# FMC_Clocks.net
KiCad netlist of a schematic drawn in Altium Designer
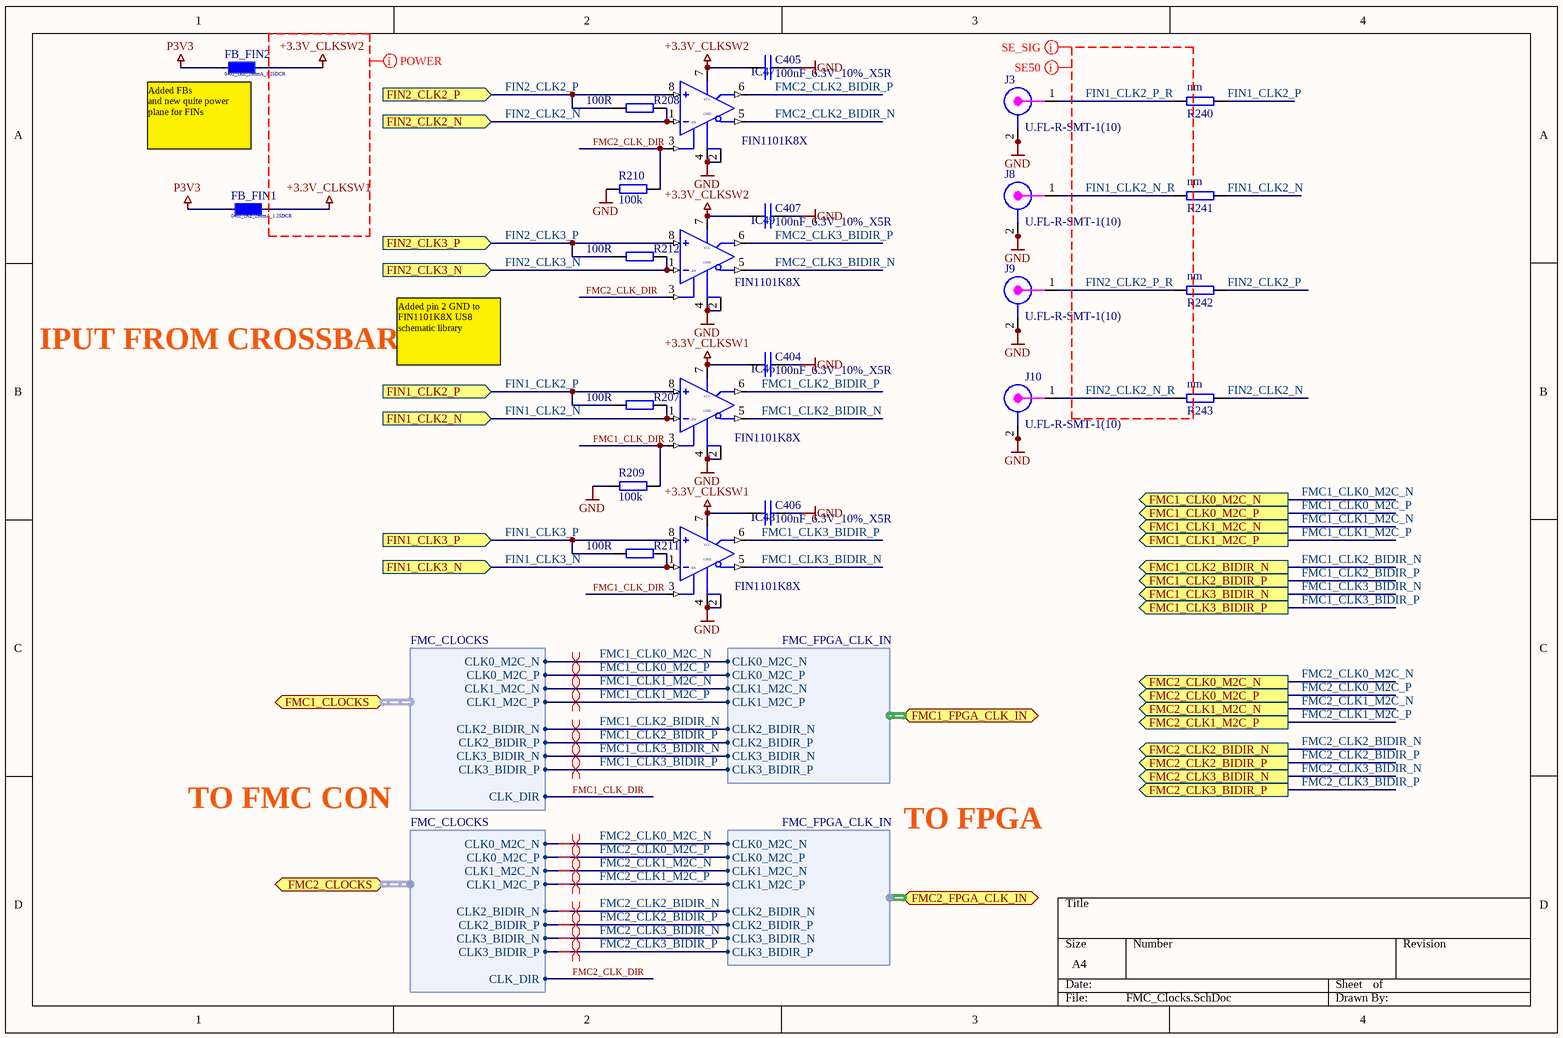
[diagram p0: FMC_Clocks.SchDoc]

(export (version "E")
  (design (tool "Eeschema 10.0.6"))
  (components
    (comp (ref "C404")
      (value "100nF_6.3V_10%_X5R")
      (footprint "0201C")
      (description "Capacitor SMD")
      (libsource (lib "LIBRARY_SCH") (part "CAP_SMD_0201"))
    )
    (comp (ref "C405")
      (value "100nF_6.3V_10%_X5R")
      (footprint "0201C")
      (description "Capacitor SMD")
      (libsource (lib "LIBRARY_SCH") (part "CAP_SMD_0201"))
    )
    (comp (ref "C406")
      (value "100nF_6.3V_10%_X5R")
      (footprint "0201C")
      (description "Capacitor SMD")
      (libsource (lib "LIBRARY_SCH") (part "CAP_SMD_0201"))
    )
    (comp (ref "C407")
      (value "100nF_6.3V_10%_X5R")
      (footprint "0201C")
      (description "Capacitor SMD")
      (libsource (lib "LIBRARY_SCH") (part "CAP_SMD_0201"))
    )
    (comp (ref "FB_FIN1")
      (value "0402_1KZ_250mA_1.25DCR")
      (footprint "INDC1005X55N")
      (description "FILTER CHIP 1000 OHM 250MA 0402")
      (fields
        (field (name "PART NUMBER") "BLM15HD102SN1D")
        (field (name "MANUFACTURER") "Murata Electronics North America")
      )
      (libsource (lib "Filters") (part "Ferrite Bead 2-pin"))
    )
    (comp (ref "FB_FIN2")
      (value "0402_1KZ_250mA_1.25DCR")
      (footprint "INDC1005X55N")
      (description "FILTER CHIP 1000 OHM 250MA 0402")
      (fields
        (field (name "PART NUMBER") "BLM15HD102SN1D")
        (field (name "MANUFACTURER") "Murata Electronics North America")
      )
      (libsource (lib "Filters") (part "Ferrite Bead 2-pin"))
    )
    (comp (ref "IC46")
      (value "FIN1101K8X")
      (footprint "US8")
      (description "LVDS TO LVDS repeater3.3V")
      (libsource (lib "AMC_FMC_Carrier") (part "IFC_FIN1101K8X"))
    )
    (comp (ref "IC47")
      (value "FIN1101K8X")
      (footprint "US8")
      (description "LVDS TO LVDS repeater3.3V")
      (libsource (lib "AMC_FMC_Carrier") (part "IFC_FIN1101K8X"))
    )
    (comp (ref "IC48")
      (value "FIN1101K8X")
      (footprint "US8")
      (description "LVDS TO LVDS repeater3.3V")
      (libsource (lib "AMC_FMC_Carrier") (part "IFC_FIN1101K8X"))
    )
    (comp (ref "IC49")
      (value "FIN1101K8X")
      (footprint "US8")
      (description "LVDS TO LVDS repeater3.3V")
      (libsource (lib "AMC_FMC_Carrier") (part "IFC_FIN1101K8X"))
    )
    (comp (ref "J3")
      (value "U.FL-R-SMT-1(10)")
      (footprint "CON_UFL_HIROSE_RECEPTACLE")
      (description "UFL")
      (libsource (lib "LIBRARY_SCH") (part "CON_UFL_SMD"))
    )
    (comp (ref "J8")
      (value "U.FL-R-SMT-1(10)")
      (footprint "CON_UFL_HIROSE_RECEPTACLE")
      (description "UFL")
      (libsource (lib "LIBRARY_SCH") (part "CON_UFL_SMD"))
    )
    (comp (ref "J9")
      (value "U.FL-R-SMT-1(10)")
      (footprint "CON_UFL_HIROSE_RECEPTACLE")
      (description "UFL")
      (libsource (lib "LIBRARY_SCH") (part "CON_UFL_SMD"))
    )
    (comp (ref "J10")
      (value "U.FL-R-SMT-1(10)")
      (footprint "CON_UFL_HIROSE_RECEPTACLE")
      (description "UFL")
      (libsource (lib "LIBRARY_SCH") (part "CON_UFL_SMD"))
    )
    (comp (ref "R207")
      (value "100R")
      (footprint "0402R")
      (description "SMD Resistor")
      (libsource (lib "LIBRARY_SCH") (part "RES_0402"))
    )
    (comp (ref "R208")
      (value "100R")
      (footprint "0402R")
      (description "SMD Resistor")
      (libsource (lib "LIBRARY_SCH") (part "RES_0402"))
    )
    (comp (ref "R209")
      (value "100k")
      (footprint "0402R")
      (description "SMD Resistor")
      (libsource (lib "LIBRARY_SCH") (part "RES_0402"))
    )
    (comp (ref "R210")
      (value "100k")
      (footprint "0402R")
      (description "SMD Resistor")
      (libsource (lib "LIBRARY_SCH") (part "RES_0402"))
    )
    (comp (ref "R211")
      (value "100R")
      (footprint "0402R")
      (description "SMD Resistor")
      (libsource (lib "LIBRARY_SCH") (part "RES_0402"))
    )
    (comp (ref "R212")
      (value "100R")
      (footprint "0402R")
      (description "SMD Resistor")
      (libsource (lib "LIBRARY_SCH") (part "RES_0402"))
    )
    (comp (ref "R240")
      (value "nm")
      (footprint "0402R")
      (description "SMD Resistor")
      (libsource (lib "LIBRARY_SCH") (part "RES_0402"))
    )
    (comp (ref "R241")
      (value "nm")
      (footprint "0402R")
      (description "SMD Resistor")
      (libsource (lib "LIBRARY_SCH") (part "RES_0402"))
    )
    (comp (ref "R242")
      (value "nm")
      (footprint "0402R")
      (description "SMD Resistor")
      (libsource (lib "LIBRARY_SCH") (part "RES_0402"))
    )
    (comp (ref "R243")
      (value "nm")
      (footprint "0402R")
      (description "SMD Resistor")
      (libsource (lib "LIBRARY_SCH") (part "RES_0402"))
    )
  )
  (nets
    (net (code "3") (name "+3.3V_CLKSW1") (class "Default")
      (node (ref "C404") (pin "1") (pinfunction "1_1") (pintype "passive"))
      (node (ref "C406") (pin "1") (pinfunction "1_1") (pintype "passive"))
      (node (ref "FB_FIN1") (pin "2") (pinfunction "-_2") (pintype "passive"))
      (node (ref "IC46") (pin "7") (pinfunction "VCC_7") (pintype "power_in"))
      (node (ref "IC48") (pin "7") (pinfunction "VCC_7") (pintype "power_in"))
    )
    (net (code "4") (name "+3.3V_CLKSW2") (class "Default")
      (node (ref "C405") (pin "1") (pinfunction "1_1") (pintype "passive"))
      (node (ref "C407") (pin "1") (pinfunction "1_1") (pintype "passive"))
      (node (ref "FB_FIN2") (pin "2") (pinfunction "-_2") (pintype "passive"))
      (node (ref "IC47") (pin "7") (pinfunction "VCC_7") (pintype "power_in"))
      (node (ref "IC49") (pin "7") (pinfunction "VCC_7") (pintype "power_in"))
    )
    (net (code "5") (name "/FIN1_CLK2_N") (class "Default")
      (node (ref "IC46") (pin "1") (pinfunction "IN_1") (pintype "input"))
      (node (ref "R207") (pin "1") (pinfunction "1_1") (pintype "passive"))
      (node (ref "R241") (pin "1") (pinfunction "1_1") (pintype "passive"))
    )
    (net (code "6") (name "/FIN1_CLK2_N_R") (class "Default")
      (node (ref "J8") (pin "1") (pintype "passive"))
      (node (ref "R241") (pin "2") (pinfunction "2_2") (pintype "passive"))
    )
    (net (code "7") (name "/FIN1_CLK2_P") (class "Default")
      (node (ref "IC46") (pin "8") (pinfunction "IN_8") (pintype "input"))
      (node (ref "R207") (pin "2") (pinfunction "2_2") (pintype "passive"))
      (node (ref "R240") (pin "1") (pinfunction "1_1") (pintype "passive"))
    )
    (net (code "8") (name "/FIN1_CLK2_P_R") (class "Default")
      (node (ref "J3") (pin "1") (pintype "passive"))
      (node (ref "R240") (pin "2") (pinfunction "2_2") (pintype "passive"))
    )
    (net (code "9") (name "/FIN1_CLK3_N") (class "Default")
      (node (ref "IC48") (pin "1") (pinfunction "IN_1") (pintype "input"))
      (node (ref "R211") (pin "1") (pinfunction "1_1") (pintype "passive"))
    )
    (net (code "10") (name "/FIN1_CLK3_P") (class "Default")
      (node (ref "IC48") (pin "8") (pinfunction "IN_8") (pintype "input"))
      (node (ref "R211") (pin "2") (pinfunction "2_2") (pintype "passive"))
    )
    (net (code "11") (name "/FIN2_CLK2_N") (class "Default")
      (node (ref "IC47") (pin "1") (pinfunction "IN_1") (pintype "input"))
      (node (ref "R208") (pin "1") (pinfunction "1_1") (pintype "passive"))
      (node (ref "R243") (pin "1") (pinfunction "1_1") (pintype "passive"))
    )
    (net (code "12") (name "/FIN2_CLK2_N_R") (class "Default")
      (node (ref "J10") (pin "1") (pintype "passive"))
      (node (ref "R243") (pin "2") (pinfunction "2_2") (pintype "passive"))
    )
    (net (code "13") (name "/FIN2_CLK2_P") (class "Default")
      (node (ref "IC47") (pin "8") (pinfunction "IN_8") (pintype "input"))
      (node (ref "R208") (pin "2") (pinfunction "2_2") (pintype "passive"))
      (node (ref "R242") (pin "1") (pinfunction "1_1") (pintype "passive"))
    )
    (net (code "14") (name "/FIN2_CLK2_P_R") (class "Default")
      (node (ref "J9") (pin "1") (pintype "passive"))
      (node (ref "R242") (pin "2") (pinfunction "2_2") (pintype "passive"))
    )
    (net (code "15") (name "/FIN2_CLK3_N") (class "Default")
      (node (ref "IC49") (pin "1") (pinfunction "IN_1") (pintype "input"))
      (node (ref "R212") (pin "1") (pinfunction "1_1") (pintype "passive"))
    )
    (net (code "16") (name "/FIN2_CLK3_P") (class "Default")
      (node (ref "IC49") (pin "8") (pinfunction "IN_8") (pintype "input"))
      (node (ref "R212") (pin "2") (pinfunction "2_2") (pintype "passive"))
    )
    (net (code "21") (name "/FMC1_CLK2_BIDIR_N") (class "Default")
      (node (ref "IC46") (pin "5") (pinfunction "~{Q}_5") (pintype "output"))
    )
    (net (code "22") (name "/FMC1_CLK2_BIDIR_P") (class "Default")
      (node (ref "IC46") (pin "6") (pinfunction "Q_6") (pintype "output"))
    )
    (net (code "23") (name "/FMC1_CLK3_BIDIR_N") (class "Default")
      (node (ref "IC48") (pin "5") (pinfunction "~{Q}_5") (pintype "output"))
    )
    (net (code "24") (name "/FMC1_CLK3_BIDIR_P") (class "Default")
      (node (ref "IC48") (pin "6") (pinfunction "Q_6") (pintype "output"))
    )
    (net (code "25") (name "/FMC1_CLK_DIR") (class "Default")
      (node (ref "IC46") (pin "3") (pinfunction "EN_3") (pintype "input"))
      (node (ref "IC48") (pin "3") (pinfunction "EN_3") (pintype "input"))
      (node (ref "R209") (pin "2") (pinfunction "2_2") (pintype "passive"))
    )
    (net (code "30") (name "/FMC2_CLK2_BIDIR_N") (class "Default")
      (node (ref "IC47") (pin "5") (pinfunction "~{Q}_5") (pintype "output"))
    )
    (net (code "31") (name "/FMC2_CLK2_BIDIR_P") (class "Default")
      (node (ref "IC47") (pin "6") (pinfunction "Q_6") (pintype "output"))
    )
    (net (code "32") (name "/FMC2_CLK3_BIDIR_N") (class "Default")
      (node (ref "IC49") (pin "5") (pinfunction "~{Q}_5") (pintype "output"))
    )
    (net (code "33") (name "/FMC2_CLK3_BIDIR_P") (class "Default")
      (node (ref "IC49") (pin "6") (pinfunction "Q_6") (pintype "output"))
    )
    (net (code "34") (name "/FMC2_CLK_DIR") (class "Default")
      (node (ref "IC47") (pin "3") (pinfunction "EN_3") (pintype "input"))
      (node (ref "IC49") (pin "3") (pinfunction "EN_3") (pintype "input"))
      (node (ref "R210") (pin "2") (pinfunction "2_2") (pintype "passive"))
    )
    (net (code "37") (name "GND") (class "Default")
      (node (ref "C404") (pin "2") (pinfunction "2_2") (pintype "passive"))
      (node (ref "C405") (pin "2") (pinfunction "2_2") (pintype "passive"))
      (node (ref "C406") (pin "2") (pinfunction "2_2") (pintype "passive"))
      (node (ref "C407") (pin "2") (pinfunction "2_2") (pintype "passive"))
      (node (ref "IC46") (pin "2") (pinfunction "GND_2") (pintype "power_in"))
      (node (ref "IC46") (pin "4") (pinfunction "GND_4") (pintype "power_in"))
      (node (ref "IC47") (pin "2") (pinfunction "GND_2") (pintype "power_in"))
      (node (ref "IC47") (pin "4") (pinfunction "GND_4") (pintype "power_in"))
      (node (ref "IC48") (pin "2") (pinfunction "GND_2") (pintype "power_in"))
      (node (ref "IC48") (pin "4") (pinfunction "GND_4") (pintype "power_in"))
      (node (ref "IC49") (pin "2") (pinfunction "GND_2") (pintype "power_in"))
      (node (ref "IC49") (pin "4") (pinfunction "GND_4") (pintype "power_in"))
      (node (ref "J10") (pin "2") (pintype "passive"))
      (node (ref "J10") (pin "2a") (pinfunction "GND_2a") (pintype "passive"))
      (node (ref "J3") (pin "2") (pintype "passive"))
      (node (ref "J3") (pin "2a") (pinfunction "GND_2a") (pintype "passive"))
      (node (ref "J8") (pin "2") (pintype "passive"))
      (node (ref "J8") (pin "2a") (pinfunction "GND_2a") (pintype "passive"))
      (node (ref "J9") (pin "2") (pintype "passive"))
      (node (ref "J9") (pin "2a") (pinfunction "GND_2a") (pintype "passive"))
      (node (ref "R209") (pin "1") (pinfunction "1_1") (pintype "passive"))
      (node (ref "R210") (pin "1") (pinfunction "1_1") (pintype "passive"))
    )
    (net (code "38") (name "P3V3") (class "Default")
      (node (ref "FB_FIN1") (pin "1") (pinfunction "+_1") (pintype "passive"))
      (node (ref "FB_FIN2") (pin "1") (pinfunction "+_1") (pintype "passive"))
    )
  )
)
